# linistepper_with_aligned_transistors_my_.net
KiCad netlist of a schematic drawn in EAGLE
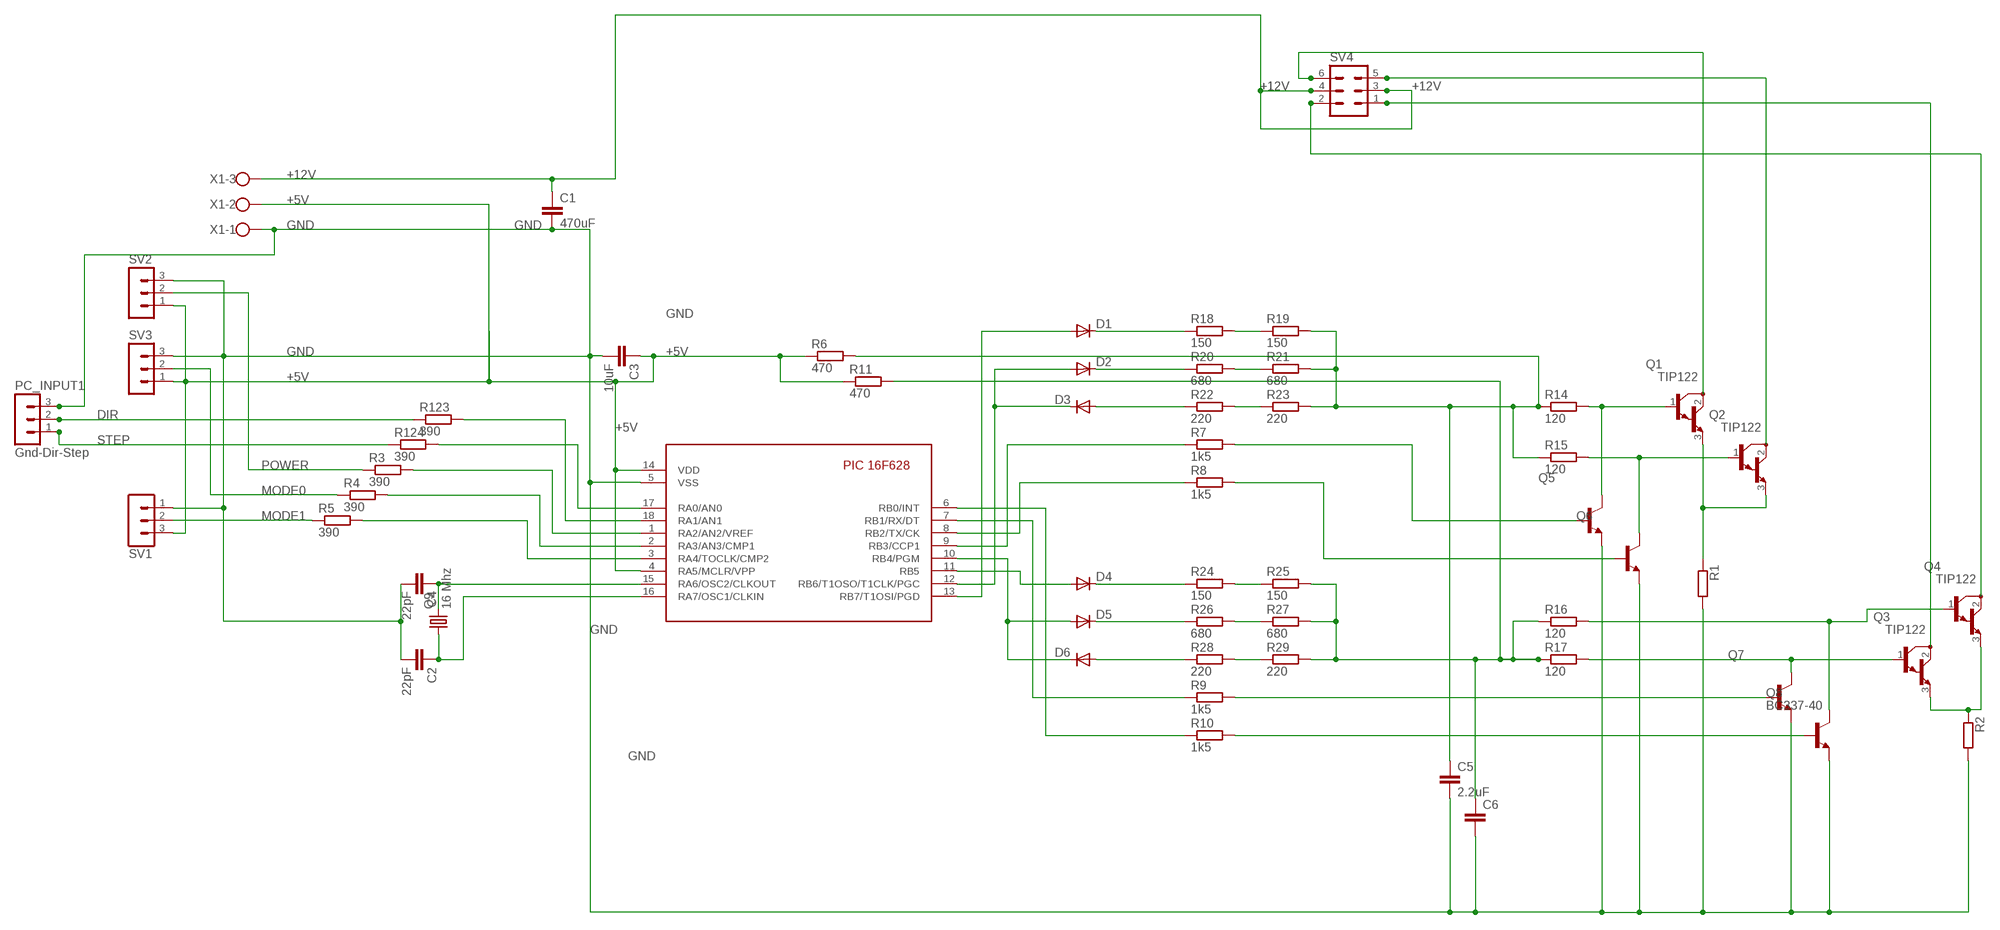
[diagram p0: schematic, sheet 1]

(export (version "E")
  (design (tool "Eeschema 10.0.6"))
  (components
    (comp (ref "C1")
      (value "470uF")
      (footprint "eagle-import:C050-045X075")
      (libsource (lib "eagle-import") (part "C-EU050-045X075"))
    )
    (comp (ref "C2")
      (value "22pF")
      (footprint "eagle-import:C025-024X044")
      (libsource (lib "eagle-import") (part "C-EU025-024X044"))
    )
    (comp (ref "C3")
      (value "10uF")
      (footprint "eagle-import:C025-040X050")
      (libsource (lib "eagle-import") (part "C-EU025-040X050"))
    )
    (comp (ref "C4")
      (value "22pF")
      (footprint "eagle-import:C025-024X044")
      (libsource (lib "eagle-import") (part "C-EU025-024X044"))
    )
    (comp (ref "C5")
      (value "2.2uF")
      (footprint "eagle-import:C050-024X044")
      (libsource (lib "eagle-import") (part "C-EU050-024X044"))
    )
    (comp (ref "C6")
      (value "C-EU050-024X044")
      (footprint "eagle-import:C050-024X044")
      (libsource (lib "eagle-import") (part "C-EU050-024X044"))
    )
    (comp (ref "D1")
      (value "1N4148")
      (footprint "eagle-import:DO35-10")
      (libsource (lib "eagle-import") (part "1N4148"))
    )
    (comp (ref "D2")
      (value "1N4148")
      (footprint "eagle-import:DO35-10")
      (libsource (lib "eagle-import") (part "1N4148"))
    )
    (comp (ref "D3")
      (value "1N4148")
      (footprint "eagle-import:DO35-10")
      (libsource (lib "eagle-import") (part "1N4148"))
    )
    (comp (ref "D4")
      (value "1N4148")
      (footprint "eagle-import:DO35-10")
      (libsource (lib "eagle-import") (part "1N4148"))
    )
    (comp (ref "D5")
      (value "1N4148")
      (footprint "eagle-import:DO35-10")
      (libsource (lib "eagle-import") (part "1N4148"))
    )
    (comp (ref "D6")
      (value "1N4148")
      (footprint "eagle-import:DO35-10")
      (libsource (lib "eagle-import") (part "1N4148"))
    )
    (comp (ref "PC_INPUT1")
      (value "Gnd-Dir-Step")
      (footprint "eagle-import:MA03-1")
      (libsource (lib "eagle-import") (part "MA03-1"))
    )
    (comp (ref "Q1")
      (value "TIP122")
      (footprint "eagle-import:TO220")
      (libsource (lib "eagle-import") (part "TIP122"))
    )
    (comp (ref "Q2")
      (value "TIP122")
      (footprint "eagle-import:TO220")
      (libsource (lib "eagle-import") (part "TIP122"))
    )
    (comp (ref "Q3")
      (value "TIP122")
      (footprint "eagle-import:TO220")
      (libsource (lib "eagle-import") (part "TIP122"))
    )
    (comp (ref "Q4")
      (value "TIP122")
      (footprint "eagle-import:TO220")
      (libsource (lib "eagle-import") (part "TIP122"))
    )
    (comp (ref "Q5")
      (value "BC337-40")
      (footprint "eagle-import:TO92")
      (libsource (lib "eagle-import") (part "BC337-40"))
    )
    (comp (ref "Q6")
      (value "BC337-40")
      (footprint "eagle-import:TO92")
      (libsource (lib "eagle-import") (part "BC337-40"))
    )
    (comp (ref "Q7")
      (value "BC337-40")
      (footprint "eagle-import:TO92")
      (libsource (lib "eagle-import") (part "BC337-40"))
    )
    (comp (ref "Q8")
      (value "BC337-40")
      (footprint "eagle-import:TO92")
      (libsource (lib "eagle-import") (part "BC337-40"))
    )
    (comp (ref "Q9")
      (value "16 Mhz")
      (footprint "eagle-import:HC49_S")
      (libsource (lib "eagle-import") (part "CRYTALHC49S"))
    )
    (comp (ref "R1")
      (value "R-EU_0922/22")
      (footprint "eagle-import:0922_22")
      (libsource (lib "eagle-import") (part "R-EU_0922/22"))
    )
    (comp (ref "R2")
      (value "R-EU_0922/22")
      (footprint "eagle-import:0922_22")
      (libsource (lib "eagle-import") (part "R-EU_0922/22"))
    )
    (comp (ref "R3")
      (value "390")
      (footprint "eagle-import:0204_7")
      (libsource (lib "eagle-import") (part "R-EU_0204/7"))
    )
    (comp (ref "R4")
      (value "390")
      (footprint "eagle-import:0204_7")
      (libsource (lib "eagle-import") (part "R-EU_0204/7"))
    )
    (comp (ref "R5")
      (value "390")
      (footprint "eagle-import:0207_5V")
      (libsource (lib "eagle-import") (part "R-EU_0207/5V"))
    )
    (comp (ref "R6")
      (value "470")
      (footprint "eagle-import:0207_10")
      (libsource (lib "eagle-import") (part "R-EU_0207/10"))
    )
    (comp (ref "R7")
      (value "1k5")
      (footprint "eagle-import:0207_10")
      (libsource (lib "eagle-import") (part "R-EU_0207/10"))
    )
    (comp (ref "R8")
      (value "1k5")
      (footprint "eagle-import:0207_10")
      (libsource (lib "eagle-import") (part "R-EU_0207/10"))
    )
    (comp (ref "R9")
      (value "1k5")
      (footprint "eagle-import:0207_10")
      (libsource (lib "eagle-import") (part "R-EU_0207/10"))
    )
    (comp (ref "R10")
      (value "1k5")
      (footprint "eagle-import:0207_10")
      (libsource (lib "eagle-import") (part "R-EU_0207/10"))
    )
    (comp (ref "R11")
      (value "470")
      (footprint "eagle-import:0207_12")
      (libsource (lib "eagle-import") (part "R-EU_0207/12"))
    )
    (comp (ref "R14")
      (value "120")
      (footprint "eagle-import:0207_10")
      (libsource (lib "eagle-import") (part "R-EU_0207/10"))
    )
    (comp (ref "R15")
      (value "120")
      (footprint "eagle-import:0207_10")
      (libsource (lib "eagle-import") (part "R-EU_0207/10"))
    )
    (comp (ref "R16")
      (value "120")
      (footprint "eagle-import:0207_10")
      (libsource (lib "eagle-import") (part "R-EU_0207/10"))
    )
    (comp (ref "R17")
      (value "120")
      (footprint "eagle-import:0207_10")
      (libsource (lib "eagle-import") (part "R-EU_0207/10"))
    )
    (comp (ref "R18")
      (value "150")
      (footprint "eagle-import:0207_2V")
      (libsource (lib "eagle-import") (part "R-EU_0207/2V"))
    )
    (comp (ref "R19")
      (value "150")
      (footprint "eagle-import:0207_2V")
      (libsource (lib "eagle-import") (part "R-EU_0207/2V"))
    )
    (comp (ref "R20")
      (value "680")
      (footprint "eagle-import:0207_2V")
      (libsource (lib "eagle-import") (part "R-EU_0207/2V"))
    )
    (comp (ref "R21")
      (value "680")
      (footprint "eagle-import:0207_2V")
      (libsource (lib "eagle-import") (part "R-EU_0207/2V"))
    )
    (comp (ref "R22")
      (value "220")
      (footprint "eagle-import:0207_2V")
      (libsource (lib "eagle-import") (part "R-EU_0207/2V"))
    )
    (comp (ref "R23")
      (value "220")
      (footprint "eagle-import:0207_2V")
      (libsource (lib "eagle-import") (part "R-EU_0207/2V"))
    )
    (comp (ref "R24")
      (value "150")
      (footprint "eagle-import:0207_2V")
      (libsource (lib "eagle-import") (part "R-EU_0207/2V"))
    )
    (comp (ref "R25")
      (value "150")
      (footprint "eagle-import:0207_2V")
      (libsource (lib "eagle-import") (part "R-EU_0207/2V"))
    )
    (comp (ref "R26")
      (value "680")
      (footprint "eagle-import:0207_2V")
      (libsource (lib "eagle-import") (part "R-EU_0207/2V"))
    )
    (comp (ref "R27")
      (value "680")
      (footprint "eagle-import:0207_2V")
      (libsource (lib "eagle-import") (part "R-EU_0207/2V"))
    )
    (comp (ref "R28")
      (value "220")
      (footprint "eagle-import:0207_2V")
      (libsource (lib "eagle-import") (part "R-EU_0207/2V"))
    )
    (comp (ref "R29")
      (value "220")
      (footprint "eagle-import:0207_2V")
      (libsource (lib "eagle-import") (part "R-EU_0207/2V"))
    )
    (comp (ref "R123")
      (value "390")
      (footprint "eagle-import:0207_2V")
      (libsource (lib "eagle-import") (part "R-EU_0207/2V"))
    )
    (comp (ref "R124")
      (value "390")
      (footprint "eagle-import:0207_2V")
      (libsource (lib "eagle-import") (part "R-EU_0207/2V"))
    )
    (comp (ref "SV1")
      (value "MA03-1")
      (footprint "eagle-import:MA03-1")
      (libsource (lib "eagle-import") (part "MA03-1"))
    )
    (comp (ref "SV2")
      (value "MA03-1")
      (footprint "eagle-import:MA03-1")
      (libsource (lib "eagle-import") (part "MA03-1"))
    )
    (comp (ref "SV3")
      (value "MA03-1")
      (footprint "eagle-import:MA03-1")
      (libsource (lib "eagle-import") (part "MA03-1"))
    )
    (comp (ref "SV4")
      (value "MA03-2")
      (footprint "eagle-import:MA03-2")
      (libsource (lib "eagle-import") (part "MA03-2"))
    )
    (comp (ref "U$1")
      (value "16F628")
      (footprint "eagle-import:PIC16F628-18-LEAD-PDIP")
      (libsource (lib "eagle-import") (part "16F628"))
    )
    (comp (ref "X1")
      (value "W237-103")
      (footprint "eagle-import:W237-103")
      (libsource (lib "eagle-import") (part "W237-103"))
    )
  )
  (nets
    (net (code "1") (name "/+5V") (class "Default")
      (node (ref "C3") (pin "1") (pinfunction "1_1") (pintype "passive"))
      (node (ref "R11") (pin "1") (pinfunction "1_1") (pintype "passive"))
      (node (ref "R6") (pin "1") (pinfunction "1_1") (pintype "passive"))
      (node (ref "SV1") (pin "3") (pinfunction "3_3") (pintype "passive"))
      (node (ref "SV2") (pin "1") (pinfunction "1_1") (pintype "passive"))
      (node (ref "SV3") (pin "1") (pinfunction "1_1") (pintype "passive"))
      (node (ref "U$1") (pin "14") (pinfunction "VDD_14") (pintype "input"))
      (node (ref "U$1") (pin "4") (pinfunction "RA5/MCLR/VPP_4") (pintype "bidirectional"))
      (node (ref "X1") (pin "2") (pinfunction "KL_2") (pintype "passive"))
    )
    (net (code "2") (name "/+12V") (class "Default")
      (node (ref "C1") (pin "1") (pinfunction "1_1") (pintype "passive"))
      (node (ref "SV4") (pin "3") (pinfunction "3_3") (pintype "passive"))
      (node (ref "SV4") (pin "4") (pinfunction "4_4") (pintype "passive"))
      (node (ref "X1") (pin "3") (pinfunction "KL_3") (pintype "passive"))
    )
    (net (code "3") (name "/DIR") (class "Default")
      (node (ref "PC_INPUT1") (pin "2") (pinfunction "2_2") (pintype "passive"))
      (node (ref "R123") (pin "1") (pinfunction "1_1") (pintype "passive"))
    )
    (net (code "4") (name "/GND") (class "Default")
      (node (ref "C1") (pin "2") (pinfunction "2_2") (pintype "passive"))
      (node (ref "C2") (pin "2") (pinfunction "2_2") (pintype "passive"))
      (node (ref "C3") (pin "2") (pinfunction "2_2") (pintype "passive"))
      (node (ref "C4") (pin "2") (pinfunction "2_2") (pintype "passive"))
      (node (ref "C5") (pin "2") (pinfunction "2_2") (pintype "passive"))
      (node (ref "C6") (pin "2") (pinfunction "2_2") (pintype "passive"))
      (node (ref "PC_INPUT1") (pin "3") (pinfunction "3_3") (pintype "passive"))
      (node (ref "Q5") (pin "1") (pinfunction "E_1") (pintype "passive"))
      (node (ref "Q6") (pin "1") (pinfunction "E_1") (pintype "passive"))
      (node (ref "Q7") (pin "1") (pinfunction "E_1") (pintype "passive"))
      (node (ref "Q8") (pin "1") (pinfunction "E_1") (pintype "passive"))
      (node (ref "R1") (pin "2") (pinfunction "2_2") (pintype "passive"))
      (node (ref "R2") (pin "2") (pinfunction "2_2") (pintype "passive"))
      (node (ref "SV1") (pin "1") (pinfunction "1_1") (pintype "passive"))
      (node (ref "SV2") (pin "3") (pinfunction "3_3") (pintype "passive"))
      (node (ref "SV3") (pin "3") (pinfunction "3_3") (pintype "passive"))
      (node (ref "U$1") (pin "5") (pinfunction "VSS_5") (pintype "input"))
      (node (ref "X1") (pin "1") (pinfunction "KL_1") (pintype "passive"))
    )
    (net (code "5") (name "/MODE0") (class "Default")
      (node (ref "R4") (pin "1") (pinfunction "1_1") (pintype "passive"))
      (node (ref "SV3") (pin "2") (pinfunction "2_2") (pintype "passive"))
    )
    (net (code "6") (name "/MODE1") (class "Default")
      (node (ref "R5") (pin "1") (pinfunction "1_1") (pintype "passive"))
      (node (ref "SV1") (pin "2") (pinfunction "2_2") (pintype "passive"))
    )
    (net (code "7") (name "/POWER") (class "Default")
      (node (ref "R3") (pin "1") (pinfunction "1_1") (pintype "passive"))
      (node (ref "SV2") (pin "2") (pinfunction "2_2") (pintype "passive"))
    )
    (net (code "8") (name "/STEP") (class "Default")
      (node (ref "PC_INPUT1") (pin "1") (pinfunction "1_1") (pintype "passive"))
      (node (ref "R124") (pin "1") (pinfunction "1_1") (pintype "passive"))
    )
    (net (code "9") (name "Net-(C5-Pad1)") (class "Default")
      (node (ref "C5") (pin "1") (pinfunction "1_1") (pintype "passive"))
      (node (ref "R14") (pin "1") (pinfunction "1_1") (pintype "passive"))
      (node (ref "R15") (pin "1") (pinfunction "1_1") (pintype "passive"))
      (node (ref "R19") (pin "2") (pinfunction "2_2") (pintype "passive"))
      (node (ref "R21") (pin "2") (pinfunction "2_2") (pintype "passive"))
      (node (ref "R23") (pin "2") (pinfunction "2_2") (pintype "passive"))
      (node (ref "R6") (pin "2") (pinfunction "2_2") (pintype "passive"))
    )
    (net (code "10") (name "Net-(C6-Pad1)") (class "Default")
      (node (ref "C6") (pin "1") (pinfunction "1_1") (pintype "passive"))
      (node (ref "R11") (pin "2") (pinfunction "2_2") (pintype "passive"))
      (node (ref "R16") (pin "1") (pinfunction "1_1") (pintype "passive"))
      (node (ref "R17") (pin "1") (pinfunction "1_1") (pintype "passive"))
      (node (ref "R25") (pin "2") (pinfunction "2_2") (pintype "passive"))
      (node (ref "R27") (pin "2") (pinfunction "2_2") (pintype "passive"))
      (node (ref "R29") (pin "2") (pinfunction "2_2") (pintype "passive"))
    )
    (net (code "11") (name "Net-(D1-PadC)") (class "Default")
      (node (ref "D1") (pin "C") (pinfunction "C_C") (pintype "passive"))
      (node (ref "R18") (pin "1") (pinfunction "1_1") (pintype "passive"))
    )
    (net (code "12") (name "Net-(D2-PadC)") (class "Default")
      (node (ref "D2") (pin "C") (pinfunction "C_C") (pintype "passive"))
      (node (ref "R20") (pin "1") (pinfunction "1_1") (pintype "passive"))
    )
    (net (code "13") (name "Net-(D3-PadA)") (class "Default")
      (node (ref "D3") (pin "A") (pinfunction "A_A") (pintype "passive"))
      (node (ref "R22") (pin "1") (pinfunction "1_1") (pintype "passive"))
    )
    (net (code "14") (name "Net-(D4-PadC)") (class "Default")
      (node (ref "D4") (pin "C") (pinfunction "C_C") (pintype "passive"))
      (node (ref "R24") (pin "1") (pinfunction "1_1") (pintype "passive"))
    )
    (net (code "15") (name "Net-(D5-PadC)") (class "Default")
      (node (ref "D5") (pin "C") (pinfunction "C_C") (pintype "passive"))
      (node (ref "R26") (pin "1") (pinfunction "1_1") (pintype "passive"))
    )
    (net (code "16") (name "Net-(D6-PadA)") (class "Default")
      (node (ref "D6") (pin "A") (pinfunction "A_A") (pintype "passive"))
      (node (ref "R28") (pin "1") (pinfunction "1_1") (pintype "passive"))
    )
    (net (code "17") (name "Net-(Q1-B)") (class "Default")
      (node (ref "Q1") (pin "1") (pinfunction "B_1") (pintype "passive"))
      (node (ref "Q5") (pin "3") (pinfunction "C_3") (pintype "passive"))
      (node (ref "R14") (pin "2") (pinfunction "2_2") (pintype "passive"))
    )
    (net (code "18") (name "Net-(Q1-C)") (class "Default")
      (node (ref "Q1") (pin "2") (pinfunction "C_2") (pintype "passive"))
      (node (ref "SV4") (pin "6") (pinfunction "6_6") (pintype "passive"))
    )
    (net (code "19") (name "Net-(Q1-E)") (class "Default")
      (node (ref "Q1") (pin "3") (pinfunction "E_3") (pintype "passive"))
      (node (ref "Q2") (pin "3") (pinfunction "E_3") (pintype "passive"))
      (node (ref "R1") (pin "1") (pinfunction "1_1") (pintype "passive"))
    )
    (net (code "20") (name "Net-(Q2-B)") (class "Default")
      (node (ref "Q2") (pin "1") (pinfunction "B_1") (pintype "passive"))
      (node (ref "Q6") (pin "3") (pinfunction "C_3") (pintype "passive"))
      (node (ref "R15") (pin "2") (pinfunction "2_2") (pintype "passive"))
    )
    (net (code "21") (name "Net-(Q2-C)") (class "Default")
      (node (ref "Q2") (pin "2") (pinfunction "C_2") (pintype "passive"))
      (node (ref "SV4") (pin "5") (pinfunction "5_5") (pintype "passive"))
    )
    (net (code "22") (name "Net-(Q3-B)") (class "Default")
      (node (ref "Q3") (pin "1") (pinfunction "B_1") (pintype "passive"))
      (node (ref "Q7") (pin "3") (pinfunction "C_3") (pintype "passive"))
      (node (ref "R17") (pin "2") (pinfunction "2_2") (pintype "passive"))
    )
    (net (code "23") (name "Net-(Q3-C)") (class "Default")
      (node (ref "Q3") (pin "2") (pinfunction "C_2") (pintype "passive"))
      (node (ref "SV4") (pin "1") (pinfunction "1_1") (pintype "passive"))
    )
    (net (code "24") (name "Net-(Q3-E)") (class "Default")
      (node (ref "Q3") (pin "3") (pinfunction "E_3") (pintype "passive"))
      (node (ref "Q4") (pin "3") (pinfunction "E_3") (pintype "passive"))
      (node (ref "R2") (pin "1") (pinfunction "1_1") (pintype "passive"))
    )
    (net (code "25") (name "Net-(Q4-B)") (class "Default")
      (node (ref "Q4") (pin "1") (pinfunction "B_1") (pintype "passive"))
      (node (ref "Q8") (pin "3") (pinfunction "C_3") (pintype "passive"))
      (node (ref "R16") (pin "2") (pinfunction "2_2") (pintype "passive"))
    )
    (net (code "26") (name "Net-(Q4-C)") (class "Default")
      (node (ref "Q4") (pin "2") (pinfunction "C_2") (pintype "passive"))
      (node (ref "SV4") (pin "2") (pinfunction "2_2") (pintype "passive"))
    )
    (net (code "27") (name "Net-(Q5-B)") (class "Default")
      (node (ref "Q5") (pin "2") (pinfunction "B_2") (pintype "passive"))
      (node (ref "R7") (pin "2") (pinfunction "2_2") (pintype "passive"))
    )
    (net (code "28") (name "Net-(Q6-B)") (class "Default")
      (node (ref "Q6") (pin "2") (pinfunction "B_2") (pintype "passive"))
      (node (ref "R8") (pin "2") (pinfunction "2_2") (pintype "passive"))
    )
    (net (code "29") (name "Net-(Q7-B)") (class "Default")
      (node (ref "Q7") (pin "2") (pinfunction "B_2") (pintype "passive"))
      (node (ref "R9") (pin "2") (pinfunction "2_2") (pintype "passive"))
    )
    (net (code "30") (name "Net-(Q8-B)") (class "Default")
      (node (ref "Q8") (pin "2") (pinfunction "B_2") (pintype "passive"))
      (node (ref "R10") (pin "2") (pinfunction "2_2") (pintype "passive"))
    )
    (net (code "31") (name "Net-(R18-Pad2)") (class "Default")
      (node (ref "R18") (pin "2") (pinfunction "2_2") (pintype "passive"))
      (node (ref "R19") (pin "1") (pinfunction "1_1") (pintype "passive"))
    )
    (net (code "32") (name "Net-(R20-Pad2)") (class "Default")
      (node (ref "R20") (pin "2") (pinfunction "2_2") (pintype "passive"))
      (node (ref "R21") (pin "1") (pinfunction "1_1") (pintype "passive"))
    )
    (net (code "33") (name "Net-(R22-Pad2)") (class "Default")
      (node (ref "R22") (pin "2") (pinfunction "2_2") (pintype "passive"))
      (node (ref "R23") (pin "1") (pinfunction "1_1") (pintype "passive"))
    )
    (net (code "34") (name "Net-(R24-Pad2)") (class "Default")
      (node (ref "R24") (pin "2") (pinfunction "2_2") (pintype "passive"))
      (node (ref "R25") (pin "1") (pinfunction "1_1") (pintype "passive"))
    )
    (net (code "35") (name "Net-(R26-Pad2)") (class "Default")
      (node (ref "R26") (pin "2") (pinfunction "2_2") (pintype "passive"))
      (node (ref "R27") (pin "1") (pinfunction "1_1") (pintype "passive"))
    )
    (net (code "36") (name "Net-(R28-Pad2)") (class "Default")
      (node (ref "R28") (pin "2") (pinfunction "2_2") (pintype "passive"))
      (node (ref "R29") (pin "1") (pinfunction "1_1") (pintype "passive"))
    )
    (net (code "37") (name "Net-(U$1-RA0{slash}AN0)") (class "Default")
      (node (ref "R124") (pin "2") (pinfunction "2_2") (pintype "passive"))
      (node (ref "U$1") (pin "17") (pinfunction "RA0/AN0_17") (pintype "bidirectional"))
    )
    (net (code "38") (name "Net-(U$1-RA1{slash}AN1)") (class "Default")
      (node (ref "R123") (pin "2") (pinfunction "2_2") (pintype "passive"))
      (node (ref "U$1") (pin "18") (pinfunction "RA1/AN1_18") (pintype "bidirectional"))
    )
    (net (code "39") (name "Net-(U$1-RA2{slash}AN2{slash}VREF)") (class "Default")
      (node (ref "R3") (pin "2") (pinfunction "2_2") (pintype "passive"))
      (node (ref "U$1") (pin "1") (pinfunction "RA2/AN2/VREF_1") (pintype "bidirectional"))
    )
    (net (code "40") (name "Net-(U$1-RA3{slash}AN3{slash}CMP1)") (class "Default")
      (node (ref "R4") (pin "2") (pinfunction "2_2") (pintype "passive"))
      (node (ref "U$1") (pin "2") (pinfunction "RA3/AN3/CMP1_2") (pintype "bidirectional"))
    )
    (net (code "41") (name "Net-(U$1-RA4{slash}TOCLK{slash}CMP2)") (class "Default")
      (node (ref "R5") (pin "2") (pinfunction "2_2") (pintype "passive"))
      (node (ref "U$1") (pin "3") (pinfunction "RA4/TOCLK/CMP2_3") (pintype "bidirectional"))
    )
    (net (code "42") (name "Net-(U$1-RA6{slash}OSC2{slash}CLKOUT)") (class "Default")
      (node (ref "C4") (pin "1") (pinfunction "1_1") (pintype "passive"))
      (node (ref "Q9") (pin "2") (pinfunction "2_2") (pintype "passive"))
      (node (ref "U$1") (pin "15") (pinfunction "RA6/OSC2/CLKOUT_15") (pintype "bidirectional"))
    )
    (net (code "43") (name "Net-(U$1-RA7{slash}OSC1{slash}CLKIN)") (class "Default")
      (node (ref "C2") (pin "1") (pinfunction "1_1") (pintype "passive"))
      (node (ref "Q9") (pin "1") (pinfunction "1_1") (pintype "passive"))
      (node (ref "U$1") (pin "16") (pinfunction "RA7/OSC1/CLKIN_16") (pintype "bidirectional"))
    )
    (net (code "44") (name "Net-(U$1-RB0{slash}INT)") (class "Default")
      (node (ref "R10") (pin "1") (pinfunction "1_1") (pintype "passive"))
      (node (ref "U$1") (pin "6") (pinfunction "RB0/INT_6") (pintype "bidirectional"))
    )
    (net (code "45") (name "Net-(U$1-RB1{slash}RX{slash}DT)") (class "Default")
      (node (ref "R9") (pin "1") (pinfunction "1_1") (pintype "passive"))
      (node (ref "U$1") (pin "7") (pinfunction "RB1/RX/DT_7") (pintype "bidirectional"))
    )
    (net (code "46") (name "Net-(U$1-RB2{slash}TX{slash}CK)") (class "Default")
      (node (ref "R8") (pin "1") (pinfunction "1_1") (pintype "passive"))
      (node (ref "U$1") (pin "8") (pinfunction "RB2/TX/CK_8") (pintype "bidirectional"))
    )
    (net (code "47") (name "Net-(U$1-RB3{slash}CCP1)") (class "Default")
      (node (ref "R7") (pin "1") (pinfunction "1_1") (pintype "passive"))
      (node (ref "U$1") (pin "9") (pinfunction "RB3/CCP1_9") (pintype "bidirectional"))
    )
    (net (code "48") (name "Net-(U$1-RB4{slash}PGM)") (class "Default")
      (node (ref "D5") (pin "A") (pinfunction "A_A") (pintype "passive"))
      (node (ref "D6") (pin "C") (pinfunction "C_C") (pintype "passive"))
      (node (ref "U$1") (pin "10") (pinfunction "RB4/PGM_10") (pintype "bidirectional"))
    )
    (net (code "49") (name "Net-(U$1-RB5)") (class "Default")
      (node (ref "D4") (pin "A") (pinfunction "A_A") (pintype "passive"))
      (node (ref "U$1") (pin "11") (pinfunction "RB5_11") (pintype "bidirectional"))
    )
    (net (code "50") (name "Net-(U$1-RB6{slash}T1OSO{slash}T1CLK{slash}PGC)") (class "Default")
      (node (ref "D2") (pin "A") (pinfunction "A_A") (pintype "passive"))
      (node (ref "D3") (pin "C") (pinfunction "C_C") (pintype "passive"))
      (node (ref "U$1") (pin "12") (pinfunction "RB6/T1OSO/T1CLK/PGC_12") (pintype "bidirectional"))
    )
    (net (code "51") (name "Net-(U$1-RB7{slash}T1OSI{slash}PGD)") (class "Default")
      (node (ref "D1") (pin "A") (pinfunction "A_A") (pintype "passive"))
      (node (ref "U$1") (pin "13") (pinfunction "RB7/T1OSI/PGD_13") (pintype "bidirectional"))
    )
  )
)
